# Aqua_ph_orp.net
KiCad netlist of a schematic drawn in EAGLE
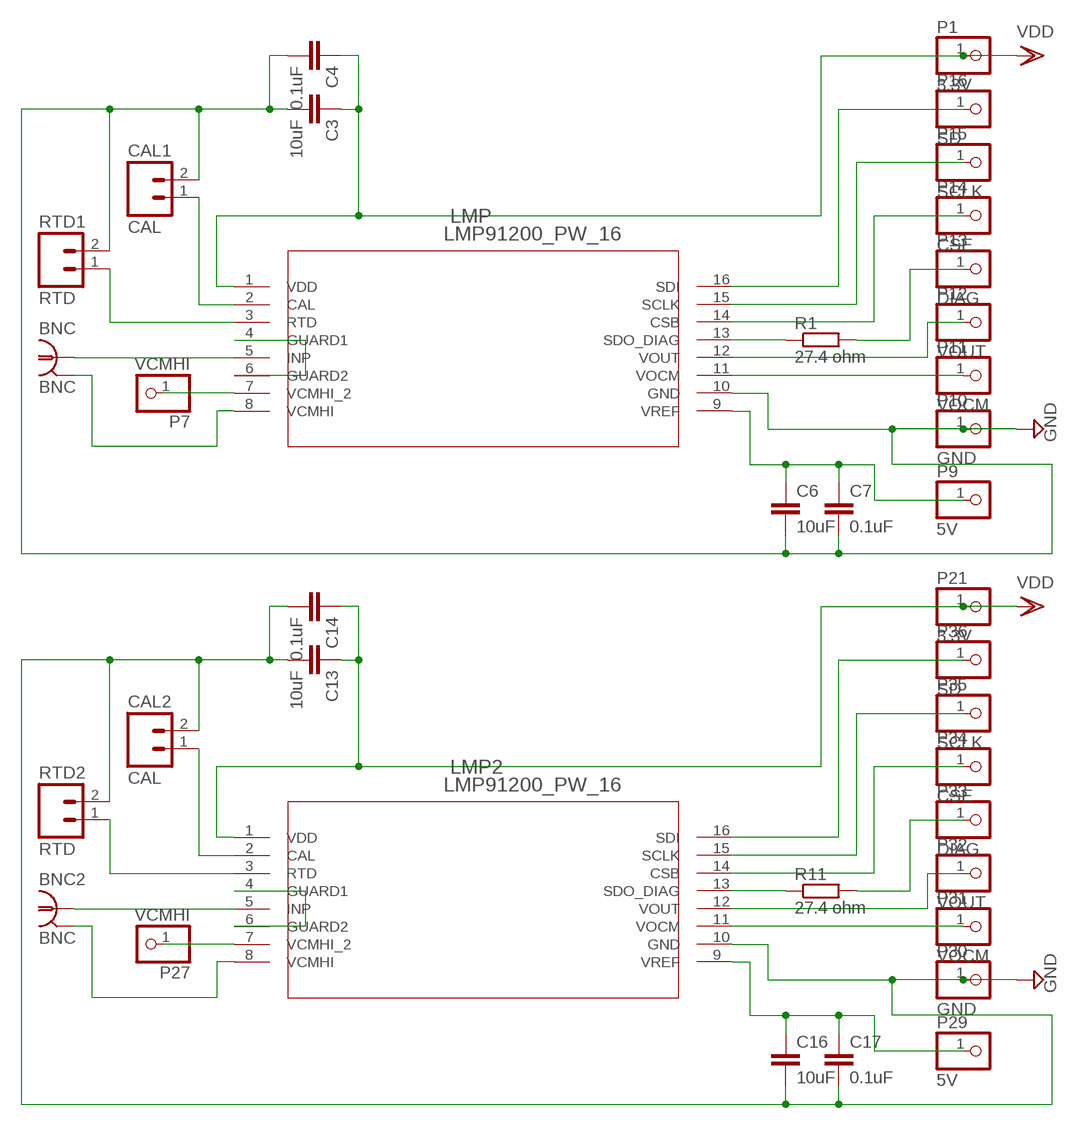
[diagram p0: schematic, sheet 1]

(export (version "E")
  (design (tool "Eeschema 10.0.6"))
  (components
    (comp (ref "BNC")
      (value "BNC")
      (footprint "eagle-import:AMP_227161")
      (fields (field (name "MF") "TYCO ELECTRONICS") (field (name "MPN") "1-227161"))
      (libsource (lib "eagle-import") (part "?2271611--0"))
    )
    (comp (ref "BNC2")
      (value "BNC")
      (footprint "eagle-import:AMP_227161")
      (fields (field (name "MF") "TYCO ELECTRONICS") (field (name "MPN") "1-227161"))
      (libsource (lib "eagle-import") (part "?2271611--0"))
    )
    (comp (ref "C3")
      (value "10uF")
      (footprint "eagle-import:C3216")
      (libsource (lib "eagle-import") (part "C-EUC3216"))
    )
    (comp (ref "C4")
      (value "0.1uF")
      (footprint "eagle-import:C0603")
      (libsource (lib "eagle-import") (part "C-EUC0603"))
    )
    (comp (ref "C6")
      (value "10uF")
      (footprint "eagle-import:C3216")
      (libsource (lib "eagle-import") (part "C-EUC3216"))
    )
    (comp (ref "C7")
      (value "0.1uF")
      (footprint "eagle-import:C1206")
      (libsource (lib "eagle-import") (part "C-EUC1206"))
    )
    (comp (ref "C13")
      (value "10uF")
      (footprint "eagle-import:C3216")
      (libsource (lib "eagle-import") (part "C-EUC3216"))
    )
    (comp (ref "C14")
      (value "0.1uF")
      (footprint "eagle-import:C0603")
      (libsource (lib "eagle-import") (part "C-EUC0603"))
    )
    (comp (ref "C16")
      (value "10uF")
      (footprint "eagle-import:C3216")
      (libsource (lib "eagle-import") (part "C-EUC3216"))
    )
    (comp (ref "C17")
      (value "0.1uF")
      (footprint "eagle-import:C1206")
      (libsource (lib "eagle-import") (part "C-EUC1206"))
    )
    (comp (ref "CAL1")
      (value "CAL")
      (footprint "eagle-import:SCREWTERMINAL-KF-301-2P")
      (libsource (lib "eagle-import") (part "M025.08MM"))
    )
    (comp (ref "CAL2")
      (value "CAL")
      (footprint "eagle-import:SCREWTERMINAL-KF-301-2P")
      (libsource (lib "eagle-import") (part "M025.08MM"))
    )
    (comp (ref "LMP")
      (value "LMP91200_PW_16")
      (footprint "eagle-import:MTC16")
      (fields
        (field (name "MANUFACTURER") "Texas Instruments")
        (field (name "MANUFACTURER_PART_NUMBER") "lmp91200_pw_16")
      )
      (libsource (lib "eagle-import") (part "LMP91200_PW_16"))
    )
    (comp (ref "LMP2")
      (value "LMP91200_PW_16")
      (footprint "eagle-import:MTC16")
      (fields
        (field (name "MANUFACTURER") "Texas Instruments")
        (field (name "MANUFACTURER_PART_NUMBER") "lmp91200_pw_16")
      )
      (libsource (lib "eagle-import") (part "LMP91200_PW_16"))
    )
    (comp (ref "P1")
      (value "3.3V")
      (footprint "eagle-import:1X01")
      (libsource (lib "eagle-import") (part "PINHD-1X1"))
    )
    (comp (ref "P7")
      (value "VCMHI")
      (footprint "eagle-import:1X01")
      (libsource (lib "eagle-import") (part "PINHD-1X1"))
    )
    (comp (ref "P9")
      (value "5V")
      (footprint "eagle-import:1X01")
      (libsource (lib "eagle-import") (part "PINHD-1X1"))
    )
    (comp (ref "P10")
      (value "GND")
      (footprint "eagle-import:1X01")
      (libsource (lib "eagle-import") (part "PINHD-1X1"))
    )
    (comp (ref "P11")
      (value "VOCM")
      (footprint "eagle-import:1X01")
      (libsource (lib "eagle-import") (part "PINHD-1X1"))
    )
    (comp (ref "P12")
      (value "VOUT")
      (footprint "eagle-import:1X01")
      (libsource (lib "eagle-import") (part "PINHD-1X1"))
    )
    (comp (ref "P13")
      (value "DIAG")
      (footprint "eagle-import:1X01")
      (libsource (lib "eagle-import") (part "PINHD-1X1"))
    )
    (comp (ref "P14")
      (value "CSE")
      (footprint "eagle-import:1X01")
      (libsource (lib "eagle-import") (part "PINHD-1X1"))
    )
    (comp (ref "P15")
      (value "SCLK")
      (footprint "eagle-import:1X01")
      (libsource (lib "eagle-import") (part "PINHD-1X1"))
    )
    (comp (ref "P16")
      (value "SD")
      (footprint "eagle-import:1X01")
      (libsource (lib "eagle-import") (part "PINHD-1X1"))
    )
    (comp (ref "P21")
      (value "3.3V")
      (footprint "eagle-import:1X01")
      (libsource (lib "eagle-import") (part "PINHD-1X1"))
    )
    (comp (ref "P27")
      (value "VCMHI")
      (footprint "eagle-import:1X01")
      (libsource (lib "eagle-import") (part "PINHD-1X1"))
    )
    (comp (ref "P29")
      (value "5V")
      (footprint "eagle-import:1X01")
      (libsource (lib "eagle-import") (part "PINHD-1X1"))
    )
    (comp (ref "P30")
      (value "GND")
      (footprint "eagle-import:1X01")
      (libsource (lib "eagle-import") (part "PINHD-1X1"))
    )
    (comp (ref "P31")
      (value "VOCM")
      (footprint "eagle-import:1X01")
      (libsource (lib "eagle-import") (part "PINHD-1X1"))
    )
    (comp (ref "P32")
      (value "VOUT")
      (footprint "eagle-import:1X01")
      (libsource (lib "eagle-import") (part "PINHD-1X1"))
    )
    (comp (ref "P33")
      (value "DIAG")
      (footprint "eagle-import:1X01")
      (libsource (lib "eagle-import") (part "PINHD-1X1"))
    )
    (comp (ref "P34")
      (value "CSE")
      (footprint "eagle-import:1X01")
      (libsource (lib "eagle-import") (part "PINHD-1X1"))
    )
    (comp (ref "P35")
      (value "SCLK")
      (footprint "eagle-import:1X01")
      (libsource (lib "eagle-import") (part "PINHD-1X1"))
    )
    (comp (ref "P36")
      (value "SD")
      (footprint "eagle-import:1X01")
      (libsource (lib "eagle-import") (part "PINHD-1X1"))
    )
    (comp (ref "R1")
      (value "27.4 ohm")
      (footprint "eagle-import:R0603")
      (libsource (lib "eagle-import") (part "R-EU_R0603"))
    )
    (comp (ref "R11")
      (value "27.4 ohm")
      (footprint "eagle-import:R0603")
      (libsource (lib "eagle-import") (part "R-EU_R0603"))
    )
    (comp (ref "RTD1")
      (value "RTD")
      (footprint "eagle-import:SCREWTERMINAL-KF-301-2P")
      (libsource (lib "eagle-import") (part "M025.08MM"))
    )
    (comp (ref "RTD2")
      (value "RTD")
      (footprint "eagle-import:SCREWTERMINAL-KF-301-2P")
      (libsource (lib "eagle-import") (part "M025.08MM"))
    )
  )
  (nets
    (net (code "1") (name "GND") (class "Default")
      (node (ref "C13") (pin "2") (pinfunction "2_2") (pintype "passive"))
      (node (ref "C14") (pin "2") (pinfunction "2_2") (pintype "passive"))
      (node (ref "C16") (pin "2") (pinfunction "2_2") (pintype "passive"))
      (node (ref "C17") (pin "2") (pinfunction "2_2") (pintype "passive"))
      (node (ref "C3") (pin "2") (pinfunction "2_2") (pintype "passive"))
      (node (ref "C4") (pin "2") (pinfunction "2_2") (pintype "passive"))
      (node (ref "C6") (pin "2") (pinfunction "2_2") (pintype "passive"))
      (node (ref "C7") (pin "2") (pinfunction "2_2") (pintype "passive"))
      (node (ref "CAL1") (pin "2") (pinfunction "2_2") (pintype "passive"))
      (node (ref "CAL2") (pin "2") (pinfunction "2_2") (pintype "passive"))
      (node (ref "LMP") (pin "10") (pinfunction "GND_10") (pintype "power_in"))
      (node (ref "LMP2") (pin "10") (pinfunction "GND_10") (pintype "power_in"))
      (node (ref "P10") (pin "1") (pinfunction "1_1") (pintype "passive"))
      (node (ref "P30") (pin "1") (pinfunction "1_1") (pintype "passive"))
      (node (ref "RTD1") (pin "2") (pinfunction "2_2") (pintype "passive"))
      (node (ref "RTD2") (pin "2") (pinfunction "2_2") (pintype "passive"))
    )
    (net (code "2") (name "Net-(BNC-GND)") (class "Default")
      (node (ref "BNC") (pin "2") (pinfunction "GND_2") (pintype "power_in"))
      (node (ref "LMP") (pin "8") (pinfunction "VCMHI_8") (pintype "output"))
    )
    (net (code "3") (name "Net-(BNC2-GND)") (class "Default")
      (node (ref "BNC2") (pin "2") (pinfunction "GND_2") (pintype "power_in"))
      (node (ref "LMP2") (pin "8") (pinfunction "VCMHI_8") (pintype "output"))
    )
    (net (code "4") (name "Net-(LMP-CAL)") (class "Default")
      (node (ref "CAL1") (pin "1") (pinfunction "1_1") (pintype "passive"))
      (node (ref "LMP") (pin "2") (pinfunction "CAL_2") (pintype "passive"))
    )
    (net (code "5") (name "Net-(LMP-CSB)") (class "Default")
      (node (ref "LMP") (pin "14") (pinfunction "CSB_14") (pintype "passive"))
      (node (ref "P14") (pin "1") (pinfunction "1_1") (pintype "passive"))
    )
    (net (code "6") (name "Net-(LMP-GUARD1)") (class "Default")
      (node (ref "LMP") (pin "4") (pinfunction "GUARD1_4") (pintype "passive"))
      (node (ref "LMP") (pin "6") (pinfunction "GUARD2_6") (pintype "passive"))
    )
    (net (code "7") (name "Net-(LMP-INP)") (class "Default")
      (node (ref "BNC") (pin "1") (pinfunction "1_1") (pintype "passive"))
      (node (ref "LMP") (pin "5") (pinfunction "INP_5") (pintype "input"))
    )
    (net (code "8") (name "Net-(LMP-RTD)") (class "Default")
      (node (ref "LMP") (pin "3") (pinfunction "RTD_3") (pintype "bidirectional"))
      (node (ref "RTD1") (pin "1") (pinfunction "1_1") (pintype "passive"))
    )
    (net (code "9") (name "Net-(LMP-SCLK)") (class "Default")
      (node (ref "LMP") (pin "15") (pinfunction "SCLK_15") (pintype "passive"))
      (node (ref "P15") (pin "1") (pinfunction "1_1") (pintype "passive"))
    )
    (net (code "10") (name "Net-(LMP-SDI)") (class "Default")
      (node (ref "LMP") (pin "16") (pinfunction "SDI_16") (pintype "passive"))
      (node (ref "P16") (pin "1") (pinfunction "1_1") (pintype "passive"))
    )
    (net (code "11") (name "Net-(LMP-SDO_DIAG)") (class "Default")
      (node (ref "LMP") (pin "13") (pinfunction "SDO_DIAG_13") (pintype "bidirectional"))
      (node (ref "R1") (pin "1") (pinfunction "1_1") (pintype "passive"))
    )
    (net (code "12") (name "Net-(LMP-VCMHI_2)") (class "Default")
      (node (ref "LMP") (pin "7") (pinfunction "VCMHI_2_7") (pintype "output"))
      (node (ref "P7") (pin "1") (pinfunction "1_1") (pintype "passive"))
    )
    (net (code "13") (name "Net-(LMP-VOCM)") (class "Default")
      (node (ref "LMP") (pin "11") (pinfunction "VOCM_11") (pintype "output"))
      (node (ref "P11") (pin "1") (pinfunction "1_1") (pintype "passive"))
    )
    (net (code "14") (name "Net-(LMP-VOUT)") (class "Default")
      (node (ref "LMP") (pin "12") (pinfunction "VOUT_12") (pintype "output"))
      (node (ref "P12") (pin "1") (pinfunction "1_1") (pintype "passive"))
    )
    (net (code "15") (name "Net-(LMP-VREF)") (class "Default")
      (node (ref "C6") (pin "1") (pinfunction "1_1") (pintype "passive"))
      (node (ref "C7") (pin "1") (pinfunction "1_1") (pintype "passive"))
      (node (ref "LMP") (pin "9") (pinfunction "VREF_9") (pintype "input"))
      (node (ref "P9") (pin "1") (pinfunction "1_1") (pintype "passive"))
    )
    (net (code "16") (name "Net-(LMP2-CAL)") (class "Default")
      (node (ref "CAL2") (pin "1") (pinfunction "1_1") (pintype "passive"))
      (node (ref "LMP2") (pin "2") (pinfunction "CAL_2") (pintype "passive"))
    )
    (net (code "17") (name "Net-(LMP2-CSB)") (class "Default")
      (node (ref "LMP2") (pin "14") (pinfunction "CSB_14") (pintype "passive"))
      (node (ref "P34") (pin "1") (pinfunction "1_1") (pintype "passive"))
    )
    (net (code "18") (name "Net-(LMP2-GUARD1)") (class "Default")
      (node (ref "LMP2") (pin "4") (pinfunction "GUARD1_4") (pintype "passive"))
      (node (ref "LMP2") (pin "6") (pinfunction "GUARD2_6") (pintype "passive"))
    )
    (net (code "19") (name "Net-(LMP2-INP)") (class "Default")
      (node (ref "BNC2") (pin "1") (pinfunction "1_1") (pintype "passive"))
      (node (ref "LMP2") (pin "5") (pinfunction "INP_5") (pintype "input"))
    )
    (net (code "20") (name "Net-(LMP2-RTD)") (class "Default")
      (node (ref "LMP2") (pin "3") (pinfunction "RTD_3") (pintype "bidirectional"))
      (node (ref "RTD2") (pin "1") (pinfunction "1_1") (pintype "passive"))
    )
    (net (code "21") (name "Net-(LMP2-SCLK)") (class "Default")
      (node (ref "LMP2") (pin "15") (pinfunction "SCLK_15") (pintype "passive"))
      (node (ref "P35") (pin "1") (pinfunction "1_1") (pintype "passive"))
    )
    (net (code "22") (name "Net-(LMP2-SDI)") (class "Default")
      (node (ref "LMP2") (pin "16") (pinfunction "SDI_16") (pintype "passive"))
      (node (ref "P36") (pin "1") (pinfunction "1_1") (pintype "passive"))
    )
    (net (code "23") (name "Net-(LMP2-SDO_DIAG)") (class "Default")
      (node (ref "LMP2") (pin "13") (pinfunction "SDO_DIAG_13") (pintype "bidirectional"))
      (node (ref "R11") (pin "1") (pinfunction "1_1") (pintype "passive"))
    )
    (net (code "24") (name "Net-(LMP2-VCMHI_2)") (class "Default")
      (node (ref "LMP2") (pin "7") (pinfunction "VCMHI_2_7") (pintype "output"))
      (node (ref "P27") (pin "1") (pinfunction "1_1") (pintype "passive"))
    )
    (net (code "25") (name "Net-(LMP2-VOCM)") (class "Default")
      (node (ref "LMP2") (pin "11") (pinfunction "VOCM_11") (pintype "output"))
      (node (ref "P31") (pin "1") (pinfunction "1_1") (pintype "passive"))
    )
    (net (code "26") (name "Net-(LMP2-VOUT)") (class "Default")
      (node (ref "LMP2") (pin "12") (pinfunction "VOUT_12") (pintype "output"))
      (node (ref "P32") (pin "1") (pinfunction "1_1") (pintype "passive"))
    )
    (net (code "27") (name "Net-(LMP2-VREF)") (class "Default")
      (node (ref "C16") (pin "1") (pinfunction "1_1") (pintype "passive"))
      (node (ref "C17") (pin "1") (pinfunction "1_1") (pintype "passive"))
      (node (ref "LMP2") (pin "9") (pinfunction "VREF_9") (pintype "input"))
      (node (ref "P29") (pin "1") (pinfunction "1_1") (pintype "passive"))
    )
    (net (code "28") (name "Net-(P13-Pad1)") (class "Default")
      (node (ref "P13") (pin "1") (pinfunction "1_1") (pintype "passive"))
      (node (ref "R1") (pin "2") (pinfunction "2_2") (pintype "passive"))
    )
    (net (code "29") (name "Net-(P33-Pad1)") (class "Default")
      (node (ref "P33") (pin "1") (pinfunction "1_1") (pintype "passive"))
      (node (ref "R11") (pin "2") (pinfunction "2_2") (pintype "passive"))
    )
    (net (code "30") (name "VDD") (class "Default")
      (node (ref "C13") (pin "1") (pinfunction "1_1") (pintype "passive"))
      (node (ref "C14") (pin "1") (pinfunction "1_1") (pintype "passive"))
      (node (ref "C3") (pin "1") (pinfunction "1_1") (pintype "passive"))
      (node (ref "C4") (pin "1") (pinfunction "1_1") (pintype "passive"))
      (node (ref "LMP") (pin "1") (pinfunction "VDD_1") (pintype "power_in"))
      (node (ref "LMP2") (pin "1") (pinfunction "VDD_1") (pintype "power_in"))
      (node (ref "P1") (pin "1") (pinfunction "1_1") (pintype "passive"))
      (node (ref "P21") (pin "1") (pinfunction "1_1") (pintype "passive"))
    )
  )
)
